# Power_Regulation.net
KiCad netlist of a schematic drawn in Altium Designer
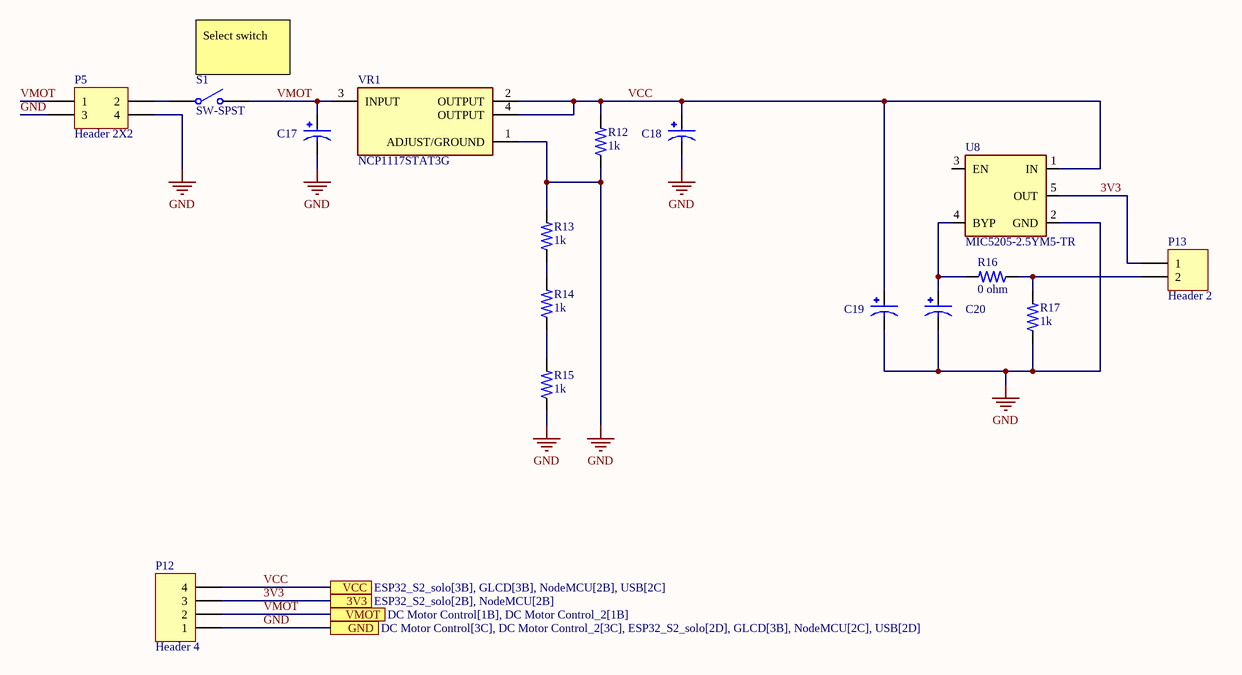
[diagram p0: Power Regulation.SchDoc]

(export (version "E")
  (design (tool "Eeschema 10.0.6"))
  (components
    (comp (ref "C17")
      (value "EEEHA1V101UP")
      (footprint "CAP_EEEHA1V101UP")
      (fields (field (name "MF") "{'manufacturer': u'Panasonic'}"))
      (libsource (lib "SnapEDA_Library") (part "EEEHA1V101UP"))
    )
    (comp (ref "C18")
      (value "EEEHA1V101UP")
      (footprint "CAP_EEEHA1V101UP")
      (fields (field (name "MF") "{'manufacturer': u'Panasonic'}"))
      (libsource (lib "SnapEDA_Library") (part "EEEHA1V101UP"))
    )
    (comp (ref "C19")
      (value "EEEHA1V101UP")
      (footprint "CAP_EEEHA1V101UP")
      (fields (field (name "MF") "{'manufacturer': u'Panasonic'}"))
      (libsource (lib "SnapEDA_Library") (part "EEEHA1V101UP"))
    )
    (comp (ref "C20")
      (value "EEEHA1V101UP")
      (footprint "CAP_EEEHA1V101UP")
      (fields (field (name "MF") "{'manufacturer': u'Panasonic'}"))
      (libsource (lib "SnapEDA_Library") (part "EEEHA1V101UP"))
    )
    (comp (ref "P5")
      (value "Header 2X2")
      (footprint "HDR2X2")
      (description "Header, 2-Pin, Dual row")
      (fields (field (name "PUBLISHER") "Altium Limited"))
      (libsource (lib "Miscellaneous Connectors") (part "Header 2X2"))
    )
    (comp (ref "P12")
      (value "Header 4")
      (footprint "HDR1X4")
      (description "Header, 4-Pin")
      (fields (field (name "PUBLISHER") "Altium Limited"))
      (libsource (lib "Miscellaneous Connectors") (part "Header 4"))
    )
    (comp (ref "P13")
      (value "Header 2")
      (footprint "HDR1X2")
      (description "Header, 2-Pin")
      (fields (field (name "PUBLISHER") "Altium Limited"))
      (libsource (lib "Miscellaneous Connectors") (part "Header 2"))
    )
    (comp (ref "R12")
      (value "1k")
      (footprint "RESC3115X65N")
      (description "RL73H 2B R43 1% 10 RL")
      (fields (field (name "MF") "{'manufacturer': u'TE Connectivity'}") (field (name "MP") "1-1879462-4"))
      (libsource (lib "SnapEDA_Library") (part "1-1879462-4"))
    )
    (comp (ref "R13")
      (value "1k")
      (footprint "RESC3115X65N")
      (description "RL73H 2B R43 1% 10 RL")
      (fields (field (name "MF") "{'manufacturer': u'TE Connectivity'}") (field (name "MP") "1-1879462-4"))
      (libsource (lib "SnapEDA_Library") (part "1-1879462-4"))
    )
    (comp (ref "R14")
      (value "1k")
      (footprint "RESC3115X65N")
      (description "RL73H 2B R43 1% 10 RL")
      (fields (field (name "MF") "{'manufacturer': u'TE Connectivity'}") (field (name "MP") "1-1879462-4"))
      (libsource (lib "SnapEDA_Library") (part "1-1879462-4"))
    )
    (comp (ref "R15")
      (value "1k")
      (footprint "RESC3115X65N")
      (description "RL73H 2B R43 1% 10 RL")
      (fields (field (name "MF") "{'manufacturer': u'TE Connectivity'}") (field (name "MP") "1-1879462-4"))
      (libsource (lib "SnapEDA_Library") (part "1-1879462-4"))
    )
    (comp (ref "R16")
      (value "0 ohm")
      (footprint "RESC3115X65N")
      (description "RL73H 2B R43 1% 10 RL")
      (fields (field (name "MF") "{'manufacturer': u'TE Connectivity'}") (field (name "MP") "1-1879462-4"))
      (libsource (lib "SnapEDA_Library") (part "1-1879462-4"))
    )
    (comp (ref "R17")
      (value "1k")
      (footprint "RESC3115X65N")
      (description "RL73H 2B R43 1% 10 RL")
      (fields (field (name "MF") "{'manufacturer': u'TE Connectivity'}") (field (name "MP") "1-1879462-4"))
      (libsource (lib "SnapEDA_Library") (part "1-1879462-4"))
    )
    (comp (ref "S1")
      (value "SW-SPST")
      (footprint "SPST-2")
      (description "Single-Pole, Single-Throw Switch")
      (fields (field (name "PUBLISHER") "Altium Limited"))
      (libsource (lib "Miscellaneous Devices") (part "SW-SPST"))
    )
    (comp (ref "U8")
      (value "MIC5205-2.5YM5-TR")
      (footprint "SOT95P280X145-5N")
      (description "MIC5205 Series 3 V Fixed Output 150 mA SMT Low-Noise LDO Regulator - SOT-23-5")
      (fields (field (name "MF") "{'manufacturer': u'Microchip Technology'}"))
      (libsource (lib "SnapEDA_Library") (part "MIC5205-2.5YM5-TR"))
    )
    (comp (ref "VR1")
      (value "NCP1117STAT3G")
      (footprint "VREG_NCP1117STAT3G")
      (description "Linear Voltage Regulator IC 1 Output 1A SOT-223")
      (fields (field (name "MF") "{'manufacturer': u'ON Semiconductor'}"))
      (libsource (lib "SnapEDA_Library") (part "NCP1117STAT3G"))
    )
  )
  (nets
    (net (code "1") (name "/3V3") (class "Default")
      (node (ref "P12") (pin "3") (pinfunction "3_3") (pintype "passive"))
      (node (ref "P13") (pin "1") (pinfunction "1_1") (pintype "passive"))
      (node (ref "U8") (pin "5") (pinfunction "OUT_5") (pintype "passive"))
    )
    (net (code "2") (name "/VCC") (class "Default")
      (node (ref "C18") (pin "1") (pinfunction "1_1") (pintype "passive"))
      (node (ref "C19") (pin "1") (pinfunction "1_1") (pintype "passive"))
      (node (ref "P12") (pin "4") (pinfunction "4_4") (pintype "passive"))
      (node (ref "R12") (pin "2") (pinfunction "2_2") (pintype "passive"))
      (node (ref "U8") (pin "1") (pinfunction "IN_1") (pintype "passive"))
      (node (ref "VR1") (pin "2") (pinfunction "OUTPUT_2") (pintype "passive"))
      (node (ref "VR1") (pin "4") (pinfunction "OUTPUT_4") (pintype "passive"))
    )
    (net (code "3") (name "/VMOT") (class "Default")
      (node (ref "C17") (pin "1") (pinfunction "1_1") (pintype "passive"))
      (node (ref "P12") (pin "2") (pinfunction "2_2") (pintype "passive"))
      (node (ref "P5") (pin "1") (pinfunction "1_1") (pintype "passive"))
      (node (ref "S1") (pin "2") (pinfunction "NO_2") (pintype "passive"))
      (node (ref "VR1") (pin "3") (pinfunction "INPUT_3") (pintype "passive"))
    )
    (net (code "4") (name "GND") (class "Default")
      (node (ref "C17") (pin "2") (pinfunction "2_2") (pintype "power_in"))
      (node (ref "C18") (pin "2") (pinfunction "2_2") (pintype "power_in"))
      (node (ref "C19") (pin "2") (pinfunction "2_2") (pintype "power_in"))
      (node (ref "C20") (pin "2") (pinfunction "2_2") (pintype "power_in"))
      (node (ref "P12") (pin "1") (pinfunction "1_1") (pintype "passive"))
      (node (ref "P5") (pin "3") (pinfunction "3_3") (pintype "passive"))
      (node (ref "P5") (pin "4") (pinfunction "4_4") (pintype "passive"))
      (node (ref "R12") (pin "1") (pinfunction "1_1") (pintype "passive"))
      (node (ref "R13") (pin "2") (pinfunction "2_2") (pintype "passive"))
      (node (ref "R15") (pin "1") (pinfunction "1_1") (pintype "passive"))
      (node (ref "R17") (pin "1") (pinfunction "1_1") (pintype "passive"))
      (node (ref "U8") (pin "2") (pinfunction "GND_2") (pintype "power_in"))
      (node (ref "VR1") (pin "1") (pinfunction "ADJUST/GROUND_1") (pintype "passive"))
    )
    (net (code "5") (name "Net-(P13-Pad2)") (class "Default")
      (node (ref "P13") (pin "2") (pinfunction "2_2") (pintype "passive"))
      (node (ref "R16") (pin "1") (pinfunction "1_1") (pintype "passive"))
      (node (ref "R17") (pin "2") (pinfunction "2_2") (pintype "passive"))
    )
    (net (code "6") (name "Net-(R13-Pad1)") (class "Default")
      (node (ref "R13") (pin "1") (pinfunction "1_1") (pintype "passive"))
      (node (ref "R14") (pin "2") (pinfunction "2_2") (pintype "passive"))
    )
    (net (code "7") (name "Net-(R14-Pad1)") (class "Default")
      (node (ref "R14") (pin "1") (pinfunction "1_1") (pintype "passive"))
      (node (ref "R15") (pin "2") (pinfunction "2_2") (pintype "passive"))
    )
    (net (code "8") (name "Net-(S1-COMMON)") (class "Default")
      (node (ref "P5") (pin "2") (pinfunction "2_2") (pintype "passive"))
      (node (ref "S1") (pin "1") (pinfunction "COMMON_1") (pintype "passive"))
    )
    (net (code "9") (name "Net-(U8-BYP)") (class "Default")
      (node (ref "C20") (pin "1") (pinfunction "1_1") (pintype "passive"))
      (node (ref "R16") (pin "2") (pinfunction "2_2") (pintype "passive"))
      (node (ref "U8") (pin "4") (pinfunction "BYP_4") (pintype "passive"))
    )
    (net (code "10") (name "unconnected-(U8-EN-Pad3)") (class "Default")
      (node (ref "U8") (pin "3") (pinfunction "EN_3") (pintype "passive"))
    )
  )
)
